# Schematic_Sheet_1.net
KiCad netlist of a schematic drawn in Altium Designer
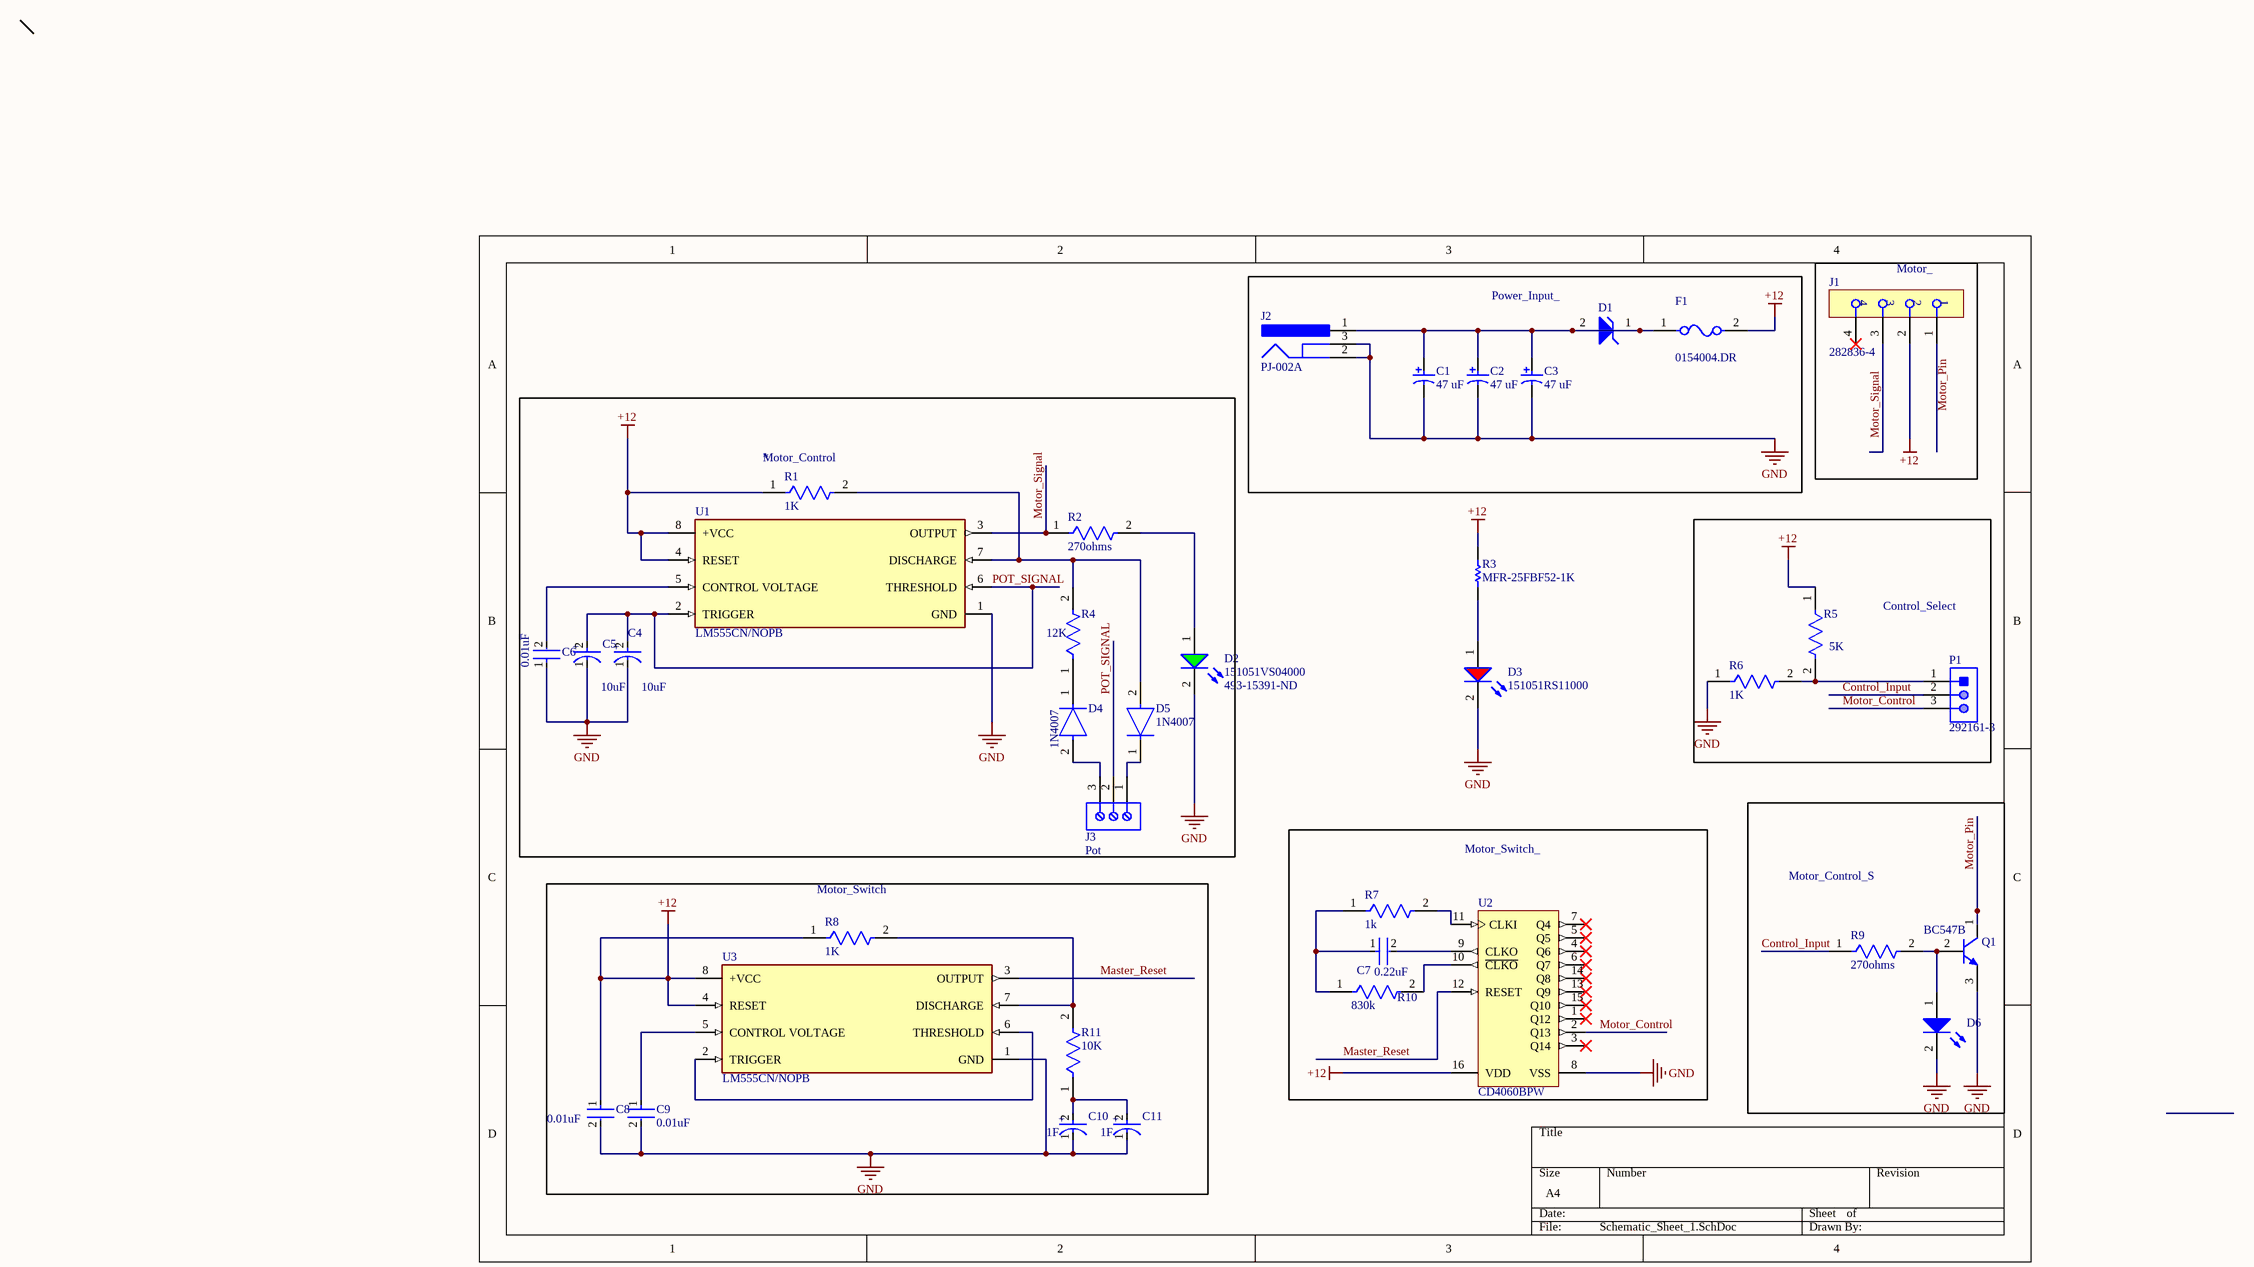
[diagram p0: Schematic_Sheet_1.SchDoc]

(export (version "E")
  (design (tool "Eeschema 10.0.6"))
  (components
    (comp (ref "C1")
      (value "47 uF")
      (footprint "NIC-UVR-5x11-2_V")
      (description "Aluminum Electrolytic Capacitor, 47 uF +/-20%, 35 V, -40 to 85 degC, 2-Pin THD, RoHS, Bulk")
      (fields (field (name "MANUFACTURER") "Nichicon") (field (name "PARTNUMBER") "UVR1V470MDD"))
      (libsource (lib "Altium Content Vault") (part "NIC-CAP-P-2"))
    )
    (comp (ref "C2")
      (value "47 uF")
      (footprint "NIC-UVR-5x11-2_V")
      (description "Aluminum Electrolytic Capacitor, 47 uF +/-20%, 35 V, -40 to 85 degC, 2-Pin THD, RoHS, Bulk")
      (fields (field (name "MANUFACTURER") "Nichicon") (field (name "PARTNUMBER") "UVR1V470MDD"))
      (libsource (lib "Altium Content Vault") (part "NIC-CAP-P-2"))
    )
    (comp (ref "C3")
      (value "47 uF")
      (footprint "NIC-UVR-5x11-2_V")
      (description "Aluminum Electrolytic Capacitor, 47 uF +/-20%, 35 V, -40 to 85 degC, 2-Pin THD, RoHS, Bulk")
      (fields (field (name "MANUFACTURER") "Nichicon") (field (name "PARTNUMBER") "UVR1V470MDD"))
      (libsource (lib "Altium Content Vault") (part "NIC-CAP-P-2"))
    )
    (comp (ref "C4")
      (value "10uF")
      (footprint "FP-RAD-TH-D_12_5_0_5-L_20-MFG")
      (description "Aluminum Electrolytic Capacitors (Radial Lead Type) 20uF ±20% 450V")
      (fields (field (name "TOLERANCE") "20%"))
      (libsource (lib "Altium Content Vault") (part "a00bbbee19879c290e62620ae7e47b1"))
    )
    (comp (ref "C5")
      (value "10uF")
      (footprint "FP-RAD-TH-D_12_5_0_5-L_20-MFG")
      (description "Aluminum Electrolytic Capacitors (Radial Lead Type) 20uF ±20% 450V")
      (fields (field (name "TOLERANCE") "20%"))
      (libsource (lib "Altium Content Vault") (part "a00bbbee19879c290e62620ae7e47b1"))
    )
    (comp (ref "C6")
      (value "0.01uF")
      (footprint "FP-C410C104M5U5TA7200-MFG")
      (description "CAP CER 0.1UF 50V Z5U AXIAL")
      (fields (field (name "TOLERANCE") "20%"))
      (libsource (lib "Altium Content Vault") (part "b4654b650e69147ec39a6b967a45e02"))
    )
    (comp (ref "C7")
      (value "0.22uF")
      (footprint "FP-C410C104M5U5TA7200-MFG")
      (description "CAP CER 0.1UF 50V Z5U AXIAL")
      (fields (field (name "TOLERANCE") "20%"))
      (libsource (lib "Altium Content Vault") (part "b4654b650e69147ec39a6b967a45e02"))
    )
    (comp (ref "C8")
      (value "0.01uF")
      (footprint "FP-C410C104M5U5TA7200-MFG")
      (description "CAP CER 0.1UF 50V Z5U AXIAL")
      (fields (field (name "TOLERANCE") "20%"))
      (libsource (lib "Altium Content Vault") (part "b4654b650e69147ec39a6b967a45e02"))
    )
    (comp (ref "C9")
      (value "0.01uF")
      (footprint "FP-C410C104M5U5TA7200-MFG")
      (description "CAP CER 0.1UF 50V Z5U AXIAL")
      (fields (field (name "TOLERANCE") "20%"))
      (libsource (lib "Altium Content Vault") (part "b4654b650e69147ec39a6b967a45e02"))
    )
    (comp (ref "C10")
      (value "1F")
      (footprint "FP-RAD-TH-D_12_5_0_5-L_20-MFG")
      (description "Aluminum Electrolytic Capacitors (Radial Lead Type) 10uF ±20% 450V")
      (fields (field (name "TOLERANCE") "20%"))
      (libsource (lib "Altium Content Vault") (part "a00bbbee19879c290e62620ae7e47b1"))
    )
    (comp (ref "C11")
      (value "1F")
      (footprint "FP-RAD-TH-D_12_5_0_5-L_20-MFG")
      (description "Aluminum Electrolytic Capacitors (Radial Lead Type) 10uF ±20% 450V")
      (fields (field (name "TOLERANCE") "20%"))
      (libsource (lib "Altium Content Vault") (part "a00bbbee19879c290e62620ae7e47b1"))
    )
    (comp (ref "D1")
      (value "P6KE36ARLG")
      (footprint "ONSC-SURMETIC40-2-017AA-01")
      (description "600 W Peak Power Transient Voltage Suppressor, 2-Pin Surmetic(TM) 40, Pb-Free, Tape and Reel")
      (fields (field (name "MANUFACTURER") "On Semiconductor"))
      (libsource (lib "Altium Content Vault") (part "ONSC-K1A2-2"))
    )
    (comp (ref "D2")
      (value "151051VS04000")
      (footprint "WL-TMRC_D5.9H8.7")
      (fields
        (field (name "SUPPLIER PART NUMBER 1") "493-15391-ND")
        (field (name "MANUFACTURER") "Nichicon")
        (field (name "MANUFACTURER PART NUMBER") "UKL1HR15KDDANA")
        (field (name "TOLERANCE") "10%")
      )
      (libsource (lib "Altium Content Vault") (part "LED_Green_1A-2K"))
    )
    (comp (ref "D3")
      (value "151051RS11000")
      (footprint "WL-TMRC_D5.9H8.7")
      (libsource (lib "Altium Content Vault") (part "LED_Red_1A-2K"))
    )
    (comp (ref "D4")
      (value "1N4007")
      (footprint "FP-1N4007-MFG")
      (description "Rectifier diode 1000 V 1 A DO-41, ,")
      (fields
        (field (name "MANUFACTURER") "Diotec")
        (field (name "OCTOPART") "https://octopart.com/1n4007-diotec-4040411")
      )
      (libsource (lib "Altium Content Vault") (part "d7152d700b627762746794eb795d46e"))
    )
    (comp (ref "D5")
      (value "1N4007")
      (footprint "FP-1N4007-MFG")
      (description "Rectifier diode 1000 V 1 A DO-41, ,")
      (fields
        (field (name "MANUFACTURER") "Diotec")
        (field (name "OCTOPART") "https://octopart.com/1n4007-diotec-4040411")
      )
      (libsource (lib "Altium Content Vault") (part "d7152d700b627762746794eb795d46e"))
    )
    (comp (ref "D6")
      (value "151051BS04000")
      (footprint "WL-TMRC_D5.9H8.7")
      (libsource (lib "Altium Content Vault") (part "LED_Blue_1A-2K"))
    )
    (comp (ref "F1")
      (value "0154004.DR")
      (footprint "FP-0154-MFG")
      (description "FUSE BRD MNT 4A 125VAC/VDC 2SMD")
      (fields
        (field (name "MANUFACTURER") "Littelfuse")
        (field (name "OCTOPART") "https://octopart.com/0154004.dr-littelfuse-565861")
      )
      (libsource (lib "Altium Content Vault") (part "5bcf9b9f640e542cf0359d10258e979"))
    )
    (comp (ref "J1")
      (value "282836-4")
      (footprint "FP-282836-4-MFG")
      (description "282836-4 Connector, Terminal Block; Wire Receptacle; 4 Pos.; 16-30 AWG; 0.197 in. CL; Sid")
      (fields (field (name "VOLTAGE") "300V"))
      (libsource (lib "Altium Content Vault") (part "282836-4"))
    )
    (comp (ref "J2")
      (value "PJ-002A")
      (footprint "CUI-PJ-002A_V")
      (fields (field (name "MANUFACTURER") "CUIInc."))
      (libsource (lib "Altium Content Vault") (part "JACK-2CD3-RN_B"))
    )
    (comp (ref "J3")
      (value "Pot")
      (footprint "691101710003")
      (fields (field (name "VOLTAGE") "250V"))
      (libsource (lib "Altium Content Vault") (part "TBL - 1R - 03P - Screw"))
    )
    (comp (ref "P1")
      (value "292161-3")
      (footprint "TECO-292161-3_V")
      (fields (field (name "MANUFACTURER") "TE Connectivity"))
      (libsource (lib "Altium Content Vault") (part "CN-1P-M-R3"))
    )
    (comp (ref "Q1")
      (value "BC547B")
      (footprint "ONSC-TO-92-3-29-11")
      (description "Amplifier Transistor, NPN Silicon, 3-Pin TO-92, Bulk Box")
      (fields (field (name "MANUFACTURER") "On Semiconductor"))
      (libsource (lib "Altium Content Vault") (part "ONSC-NPN-C1B2E3-3"))
    )
    (comp (ref "R1")
      (value "1K")
      (footprint "FP-MRS1600-MFG")
      (description "RES 20K OHM 0.4W 1% AXIAL")
      (fields (field (name "TOLERANCE") "1%"))
      (libsource (lib "Altium Content Vault") (part "1029c3af85768c4190bb7ad29bc67b5"))
    )
    (comp (ref "R2")
      (value "270ohms")
      (footprint "FP-MRS1600-MFG")
      (description "RES 20K OHM 0.4W 1% AXIAL")
      (fields (field (name "TOLERANCE") "1%"))
      (libsource (lib "Altium Content Vault") (part "1029c3af85768c4190bb7ad29bc67b5"))
    )
    (comp (ref "R3")
      (value "MFR-25FBF52-1K")
      (footprint "RESA60-630X240")
      (description "Axial Resistor, 1 KOhm, +/- 1%, 0.25W, -55 to 155 degC, 2-Pin THD, RoHS, Bulk")
      (fields (field (name "TOLERANCE") "1%"))
      (libsource (lib "Altium Content Vault") (part "RES-2"))
    )
    (comp (ref "R4")
      (value "12K")
      (footprint "FP-MRS1600-MFG")
      (description "RES 20K OHM 0.4W 1% AXIAL")
      (fields (field (name "TOLERANCE") "1%"))
      (libsource (lib "Altium Content Vault") (part "1029c3af85768c4190bb7ad29bc67b5"))
    )
    (comp (ref "R5")
      (value "5K")
      (footprint "FP-MRS1600-MFG")
      (description "RES 20K OHM 0.4W 1% AXIAL")
      (fields (field (name "TOLERANCE") "1%"))
      (libsource (lib "Altium Content Vault") (part "1029c3af85768c4190bb7ad29bc67b5"))
    )
    (comp (ref "R6")
      (value "1K")
      (footprint "FP-MRS1600-MFG")
      (description "RES 20K OHM 0.4W 1% AXIAL")
      (fields (field (name "TOLERANCE") "1%"))
      (libsource (lib "Altium Content Vault") (part "1029c3af85768c4190bb7ad29bc67b5"))
    )
    (comp (ref "R7")
      (value "1k")
      (footprint "FP-MRS1600-MFG")
      (description "RES 20K OHM 0.4W 1% AXIAL")
      (fields (field (name "TOLERANCE") "1%"))
      (libsource (lib "Altium Content Vault") (part "1029c3af85768c4190bb7ad29bc67b5"))
    )
    (comp (ref "R8")
      (value "1K")
      (footprint "FP-MRS1600-MFG")
      (description "RES 20K OHM 0.4W 1% AXIAL")
      (fields (field (name "TOLERANCE") "1%"))
      (libsource (lib "Altium Content Vault") (part "1029c3af85768c4190bb7ad29bc67b5"))
    )
    (comp (ref "R9")
      (value "270ohms")
      (footprint "FP-MRS1600-MFG")
      (description "RES 20K OHM 0.4W 1% AXIAL")
      (fields (field (name "TOLERANCE") "1%"))
      (libsource (lib "Altium Content Vault") (part "1029c3af85768c4190bb7ad29bc67b5"))
    )
    (comp (ref "R10")
      (value "830k")
      (footprint "FP-MRS1600-MFG")
      (description "RES 20K OHM 0.4W 1% AXIAL")
      (fields (field (name "TOLERANCE") "1%"))
      (libsource (lib "Altium Content Vault") (part "1029c3af85768c4190bb7ad29bc67b5"))
    )
    (comp (ref "R11")
      (value "10K")
      (footprint "FP-MRS1600-MFG")
      (description "RES 20K OHM 0.4W 1% AXIAL")
      (fields (field (name "TOLERANCE") "1%"))
      (libsource (lib "Altium Content Vault") (part "1029c3af85768c4190bb7ad29bc67b5"))
    )
    (comp (ref "U1")
      (value "LM555CN/NOPB")
      (footprint "FP-P0008A-MFG")
      (description "IC OSC SINGLE TIMER 100KHZ 8-DIP")
      (fields
        (field (name "MANUFACTURER") "Texas Instruments")
        (field (name "OCTOPART") "https://octopart.com/lm555cn%2Fnopb-texas+instruments-24814897")
      )
      (libsource (lib "Altium Content Vault") (part "8056d98efc272addb90effbbf338635"))
    )
    (comp (ref "U2")
      (value "CD4060BPW")
      (footprint "PW0016A_L")
      (fields (field (name "MANUFACTURER") "Texas Instruments"))
      (libsource (lib "Altium Content Vault") (part "TI-CD4060B-16"))
    )
    (comp (ref "U3")
      (value "LM555CN/NOPB")
      (footprint "FP-P0008A-MFG")
      (description "IC OSC SINGLE TIMER 100KHZ 8-DIP")
      (fields
        (field (name "MANUFACTURER") "Texas Instruments")
        (field (name "OCTOPART") "https://octopart.com/lm555cn%2Fnopb-texas+instruments-24814897")
      )
      (libsource (lib "Altium Content Vault") (part "8056d98efc272addb90effbbf338635"))
    )
  )
  (nets
    (net (code "1") (name "+12") (class "Default")
      (node (ref "C8") (pin "1") (pinfunction "1_1") (pintype "passive"))
      (node (ref "F1") (pin "2") (pinfunction "2_2") (pintype "passive"))
      (node (ref "J1") (pin "2") (pinfunction "2_2") (pintype "passive"))
      (node (ref "R1") (pin "1") (pinfunction "1_1") (pintype "passive"))
      (node (ref "R3") (pin "1") (pinfunction "1_1") (pintype "passive"))
      (node (ref "R5") (pin "1") (pinfunction "1_1") (pintype "passive"))
      (node (ref "R8") (pin "1") (pinfunction "1_1") (pintype "passive"))
      (node (ref "U1") (pin "4") (pinfunction "RESET_4") (pintype "input"))
      (node (ref "U1") (pin "8") (pinfunction "+VCC_8") (pintype "power_in"))
      (node (ref "U2") (pin "16") (pinfunction "VDD_16") (pintype "power_in"))
      (node (ref "U3") (pin "4") (pinfunction "RESET_4") (pintype "input"))
      (node (ref "U3") (pin "8") (pinfunction "+VCC_8") (pintype "power_in"))
    )
    (net (code "2") (name "/Control_Input") (class "Default")
      (node (ref "P1") (pin "2") (pinfunction "2_2") (pintype "passive"))
      (node (ref "R9") (pin "1") (pinfunction "1_1") (pintype "passive"))
    )
    (net (code "3") (name "/Master_Reset") (class "Default")
      (node (ref "U2") (pin "12") (pinfunction "RESET_12") (pintype "input"))
      (node (ref "U3") (pin "3") (pinfunction "OUTPUT_3") (pintype "output"))
    )
    (net (code "4") (name "/Motor_Control") (class "Default")
      (node (ref "P1") (pin "3") (pinfunction "3_3") (pintype "passive"))
      (node (ref "U2") (pin "2") (pinfunction "Q13_2") (pintype "output"))
    )
    (net (code "5") (name "/Motor_Pin") (class "Default")
      (node (ref "Q1") (pin "1") (pinfunction "C_1") (pintype "passive"))
    )
    (net (code "6") (name "/Motor_Signal") (class "Default")
      (node (ref "J1") (pin "3") (pinfunction "3_3") (pintype "passive"))
      (node (ref "R2") (pin "1") (pinfunction "1_1") (pintype "passive"))
      (node (ref "U1") (pin "3") (pinfunction "OUTPUT_3") (pintype "output"))
    )
    (net (code "7") (name "/POT_SIGNAL") (class "Default")
      (node (ref "C4") (pin "2") (pinfunction "A_2") (pintype "passive"))
      (node (ref "C5") (pin "2") (pinfunction "A_2") (pintype "passive"))
      (node (ref "J3") (pin "2") (pinfunction "2_2") (pintype "passive"))
      (node (ref "U1") (pin "2") (pinfunction "TRIGGER_2") (pintype "input"))
      (node (ref "U1") (pin "6") (pinfunction "THRESHOLD_6") (pintype "input"))
    )
    (net (code "8") (name "GND") (class "Default")
      (node (ref "C1") (pin "2") (pinfunction "2_2") (pintype "passive"))
      (node (ref "C10") (pin "1") (pinfunction "C_1") (pintype "passive"))
      (node (ref "C11") (pin "1") (pinfunction "C_1") (pintype "passive"))
      (node (ref "C2") (pin "2") (pinfunction "2_2") (pintype "passive"))
      (node (ref "C3") (pin "2") (pinfunction "2_2") (pintype "passive"))
      (node (ref "C4") (pin "1") (pinfunction "C_1") (pintype "passive"))
      (node (ref "C5") (pin "1") (pinfunction "C_1") (pintype "passive"))
      (node (ref "C6") (pin "1") (pinfunction "1_1") (pintype "passive"))
      (node (ref "C8") (pin "2") (pinfunction "2_2") (pintype "passive"))
      (node (ref "C9") (pin "2") (pinfunction "2_2") (pintype "passive"))
      (node (ref "D2") (pin "2") (pinfunction "K_2") (pintype "passive"))
      (node (ref "D3") (pin "2") (pinfunction "K_2") (pintype "passive"))
      (node (ref "D6") (pin "2") (pinfunction "K_2") (pintype "passive"))
      (node (ref "J2") (pin "2") (pinfunction "2_2") (pintype "passive"))
      (node (ref "J2") (pin "3") (pinfunction "3_3") (pintype "passive"))
      (node (ref "Q1") (pin "3") (pinfunction "E_3") (pintype "passive"))
      (node (ref "R6") (pin "1") (pinfunction "1_1") (pintype "passive"))
      (node (ref "U1") (pin "1") (pinfunction "GND_1") (pintype "power_in"))
      (node (ref "U2") (pin "8") (pinfunction "VSS_8") (pintype "power_in"))
      (node (ref "U3") (pin "1") (pinfunction "GND_1") (pintype "power_in"))
    )
    (net (code "9") (name "Net-(C7-Pad1)") (class "Default")
      (node (ref "C7") (pin "1") (pinfunction "1_1") (pintype "passive"))
      (node (ref "R10") (pin "1") (pinfunction "1_1") (pintype "passive"))
      (node (ref "R7") (pin "1") (pinfunction "1_1") (pintype "passive"))
    )
    (net (code "10") (name "Net-(C10-A)") (class "Default")
      (node (ref "C10") (pin "2") (pinfunction "A_2") (pintype "passive"))
      (node (ref "C11") (pin "2") (pinfunction "A_2") (pintype "passive"))
      (node (ref "R11") (pin "1") (pinfunction "1_1") (pintype "passive"))
    )
    (net (code "11") (name "Net-(D1-A)") (class "Default")
      (node (ref "C1") (pin "1") (pinfunction "1_1") (pintype "passive"))
      (node (ref "C2") (pin "1") (pinfunction "1_1") (pintype "passive"))
      (node (ref "C3") (pin "1") (pinfunction "1_1") (pintype "passive"))
      (node (ref "D1") (pin "1") (pinfunction "K_1") (pintype "passive"))
      (node (ref "D1") (pin "2") (pinfunction "A_2") (pintype "passive"))
      (node (ref "F1") (pin "1") (pinfunction "1_1") (pintype "passive"))
      (node (ref "J2") (pin "1") (pinfunction "1_1") (pintype "passive"))
    )
    (net (code "12") (name "Net-(D2-A)") (class "Default")
      (node (ref "D2") (pin "1") (pinfunction "A_1") (pintype "passive"))
      (node (ref "R2") (pin "2") (pinfunction "2_2") (pintype "passive"))
    )
    (net (code "13") (name "Net-(D3-A)") (class "Default")
      (node (ref "D3") (pin "1") (pinfunction "A_1") (pintype "passive"))
      (node (ref "R3") (pin "2") (pinfunction "2_2") (pintype "passive"))
    )
    (net (code "14") (name "Net-(D4-A)") (class "Default")
      (node (ref "D4") (pin "2") (pinfunction "A_2") (pintype "passive"))
      (node (ref "J3") (pin "3") (pinfunction "3_3") (pintype "passive"))
    )
    (net (code "15") (name "Net-(D4-C)") (class "Default")
      (node (ref "D4") (pin "1") (pinfunction "C_1") (pintype "passive"))
      (node (ref "R4") (pin "1") (pinfunction "1_1") (pintype "passive"))
    )
    (net (code "16") (name "Net-(D5-A)") (class "Default")
      (node (ref "D5") (pin "2") (pinfunction "A_2") (pintype "passive"))
      (node (ref "R1") (pin "2") (pinfunction "2_2") (pintype "passive"))
      (node (ref "R4") (pin "2") (pinfunction "2_2") (pintype "passive"))
      (node (ref "U1") (pin "7") (pinfunction "DISCHARGE_7") (pintype "input"))
    )
    (net (code "17") (name "Net-(D5-C)") (class "Default")
      (node (ref "D5") (pin "1") (pinfunction "C_1") (pintype "passive"))
      (node (ref "J3") (pin "1") (pinfunction "1_1") (pintype "passive"))
    )
    (net (code "18") (name "Net-(D6-A)") (class "Default")
      (node (ref "D6") (pin "1") (pinfunction "A_1") (pintype "passive"))
      (node (ref "Q1") (pin "2") (pinfunction "B_2") (pintype "passive"))
      (node (ref "R9") (pin "2") (pinfunction "2_2") (pintype "passive"))
    )
    (net (code "19") (name "Net-(P1-Pad1)") (class "Default")
      (node (ref "P1") (pin "1") (pinfunction "1_1") (pintype "passive"))
      (node (ref "R5") (pin "2") (pinfunction "2_2") (pintype "passive"))
      (node (ref "R6") (pin "2") (pinfunction "2_2") (pintype "passive"))
    )
    (net (code "20") (name "Net-(U1-CONTROL_VOLTAGE)") (class "Default")
      (node (ref "C6") (pin "2") (pinfunction "2_2") (pintype "passive"))
      (node (ref "U1") (pin "5") (pinfunction "CONTROL_VOLTAGE_5") (pintype "input"))
    )
    (net (code "21") (name "Net-(U2-CLKI)") (class "Default")
      (node (ref "R7") (pin "2") (pinfunction "2_2") (pintype "passive"))
      (node (ref "U2") (pin "11") (pinfunction "CLKI_11") (pintype "input"))
    )
    (net (code "22") (name "Net-(U2-CLKO)") (class "Default")
      (node (ref "C7") (pin "2") (pinfunction "2_2") (pintype "passive"))
      (node (ref "U2") (pin "9") (pinfunction "CLKO_9") (pintype "output"))
    )
    (net (code "23") (name "Net-(U2-~{CLKO})") (class "Default")
      (node (ref "R10") (pin "2") (pinfunction "2_2") (pintype "passive"))
      (node (ref "U2") (pin "10") (pinfunction "~{CLKO}_10") (pintype "output"))
    )
    (net (code "24") (name "Net-(U3-CONTROL_VOLTAGE)") (class "Default")
      (node (ref "C9") (pin "1") (pinfunction "1_1") (pintype "passive"))
      (node (ref "U3") (pin "5") (pinfunction "CONTROL_VOLTAGE_5") (pintype "input"))
    )
    (net (code "25") (name "Net-(U3-DISCHARGE)") (class "Default")
      (node (ref "R11") (pin "2") (pinfunction "2_2") (pintype "passive"))
      (node (ref "R8") (pin "2") (pinfunction "2_2") (pintype "passive"))
      (node (ref "U3") (pin "7") (pinfunction "DISCHARGE_7") (pintype "input"))
    )
    (net (code "26") (name "Net-(U3-THRESHOLD)") (class "Default")
      (node (ref "U3") (pin "2") (pinfunction "TRIGGER_2") (pintype "input"))
      (node (ref "U3") (pin "6") (pinfunction "THRESHOLD_6") (pintype "input"))
    )
    (net (code "27") (name "unconnected-(J1-Pad1)") (class "Default")
      (node (ref "J1") (pin "1") (pinfunction "1_1") (pintype "passive"))
    )
    (net (code "28") (name "unconnected-(J1-Pad4)") (class "Default")
      (node (ref "J1") (pin "4") (pinfunction "4_4") (pintype "passive+no_connect"))
    )
    (net (code "29") (name "unconnected-(U2-Q4-Pad7)") (class "Default")
      (node (ref "U2") (pin "7") (pinfunction "Q4_7") (pintype "output+no_connect"))
    )
    (net (code "30") (name "unconnected-(U2-Q5-Pad5)") (class "Default")
      (node (ref "U2") (pin "5") (pinfunction "Q5_5") (pintype "output+no_connect"))
    )
    (net (code "31") (name "unconnected-(U2-Q6-Pad4)") (class "Default")
      (node (ref "U2") (pin "4") (pinfunction "Q6_4") (pintype "output+no_connect"))
    )
    (net (code "32") (name "unconnected-(U2-Q7-Pad6)") (class "Default")
      (node (ref "U2") (pin "6") (pinfunction "Q7_6") (pintype "output+no_connect"))
    )
    (net (code "33") (name "unconnected-(U2-Q8-Pad14)") (class "Default")
      (node (ref "U2") (pin "14") (pinfunction "Q8_14") (pintype "output+no_connect"))
    )
    (net (code "34") (name "unconnected-(U2-Q9-Pad13)") (class "Default")
      (node (ref "U2") (pin "13") (pinfunction "Q9_13") (pintype "output+no_connect"))
    )
    (net (code "35") (name "unconnected-(U2-Q10-Pad15)") (class "Default")
      (node (ref "U2") (pin "15") (pinfunction "Q10_15") (pintype "output+no_connect"))
    )
    (net (code "36") (name "unconnected-(U2-Q12-Pad1)") (class "Default")
      (node (ref "U2") (pin "1") (pinfunction "Q12_1") (pintype "output+no_connect"))
    )
    (net (code "37") (name "unconnected-(U2-Q14-Pad3)") (class "Default")
      (node (ref "U2") (pin "3") (pinfunction "Q14_3") (pintype "output+no_connect"))
    )
  )
)
